# MCU.net
KiCad netlist of a schematic drawn in Altium Designer
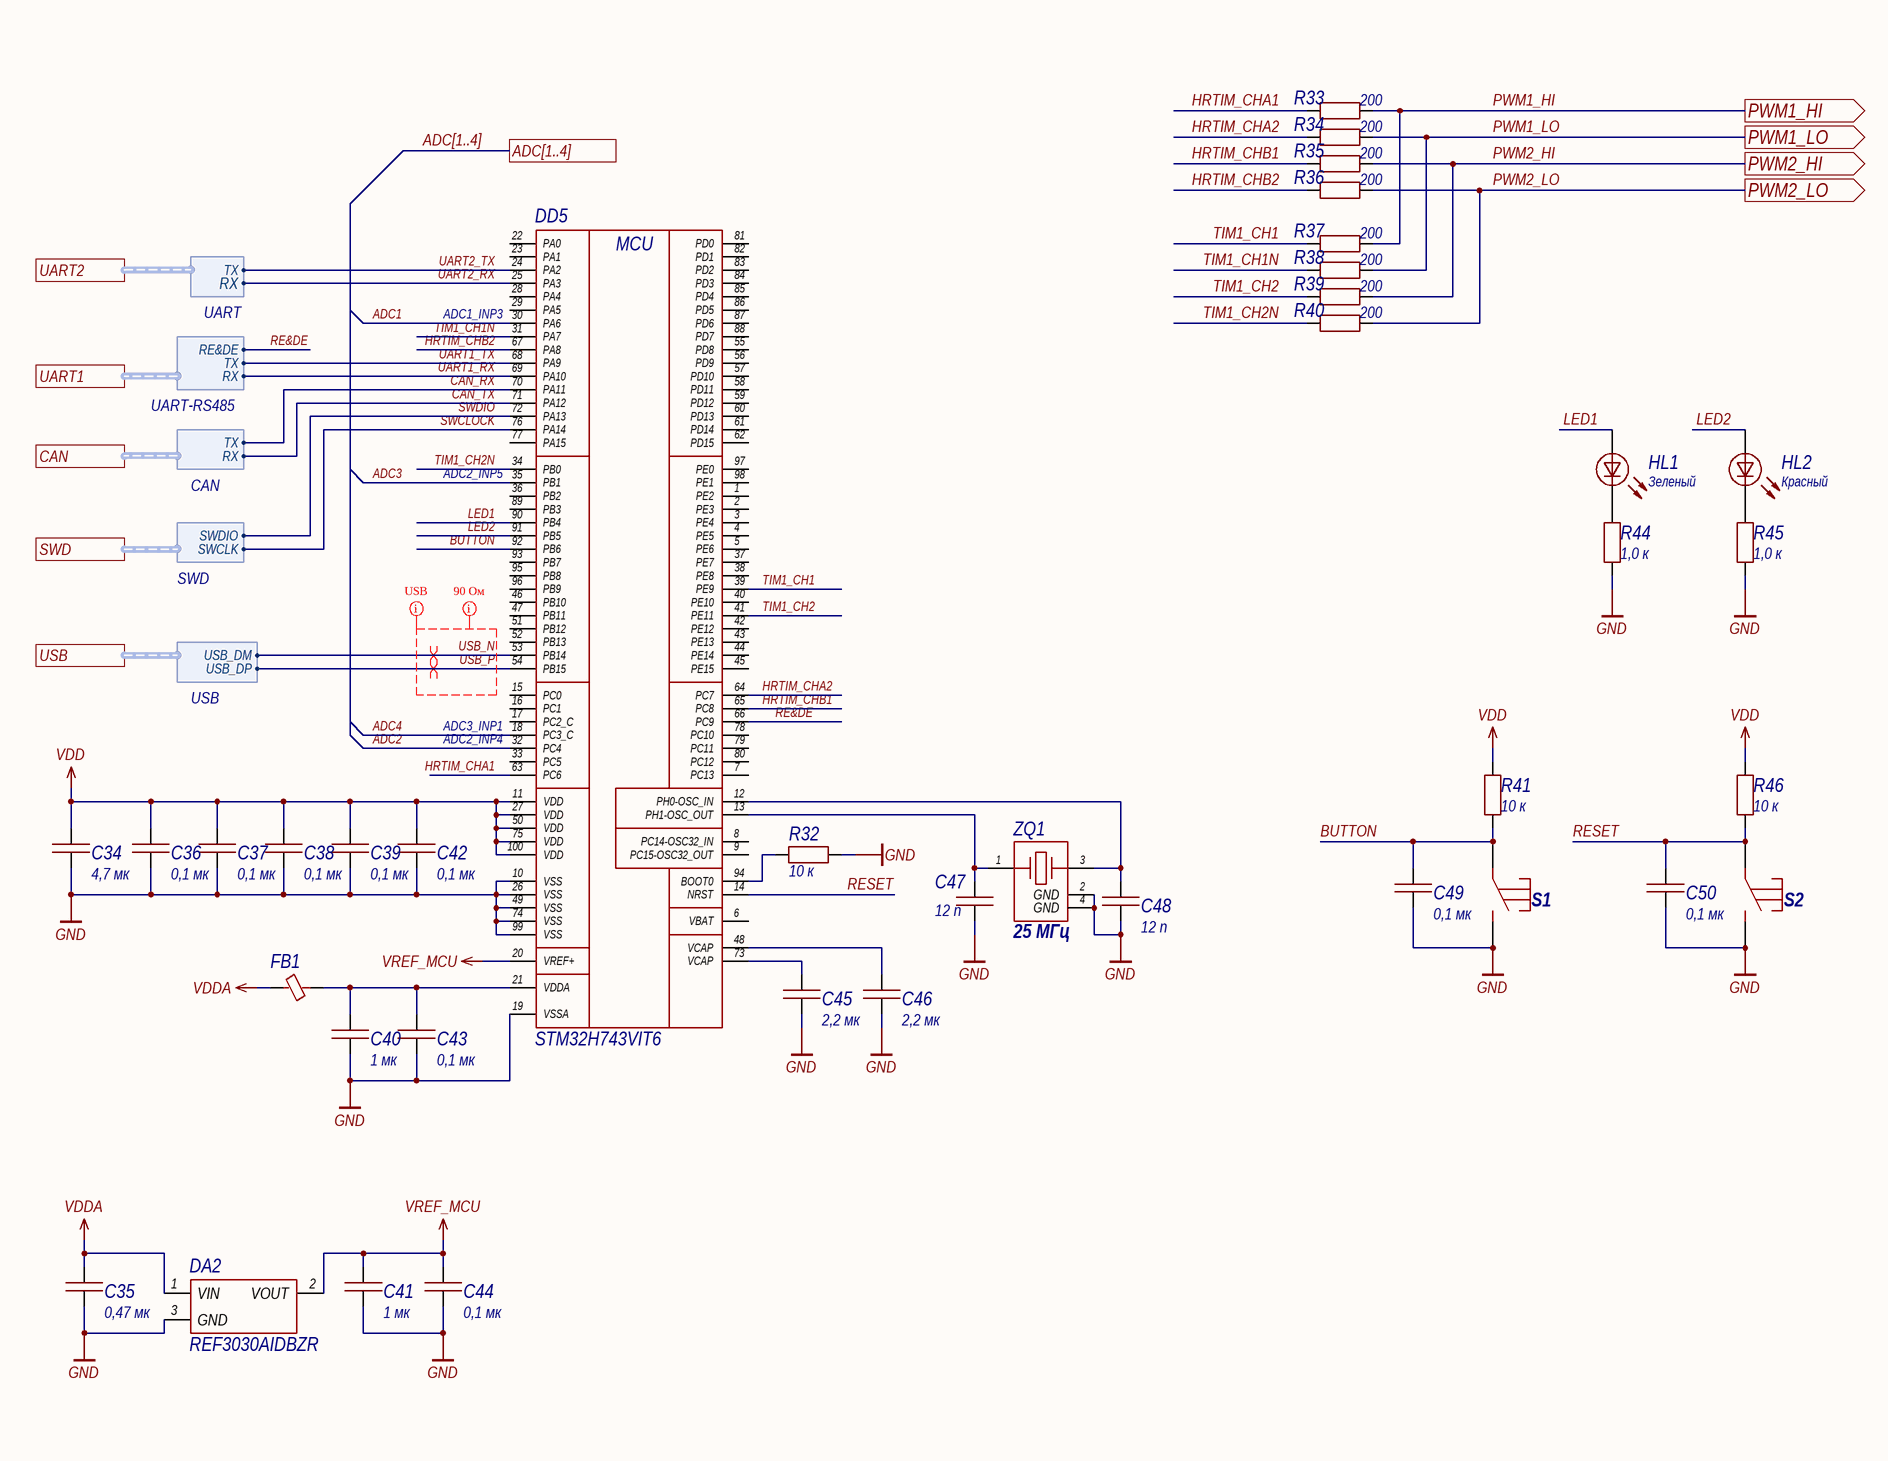
[diagram p0: MCU.SchDoc, left]
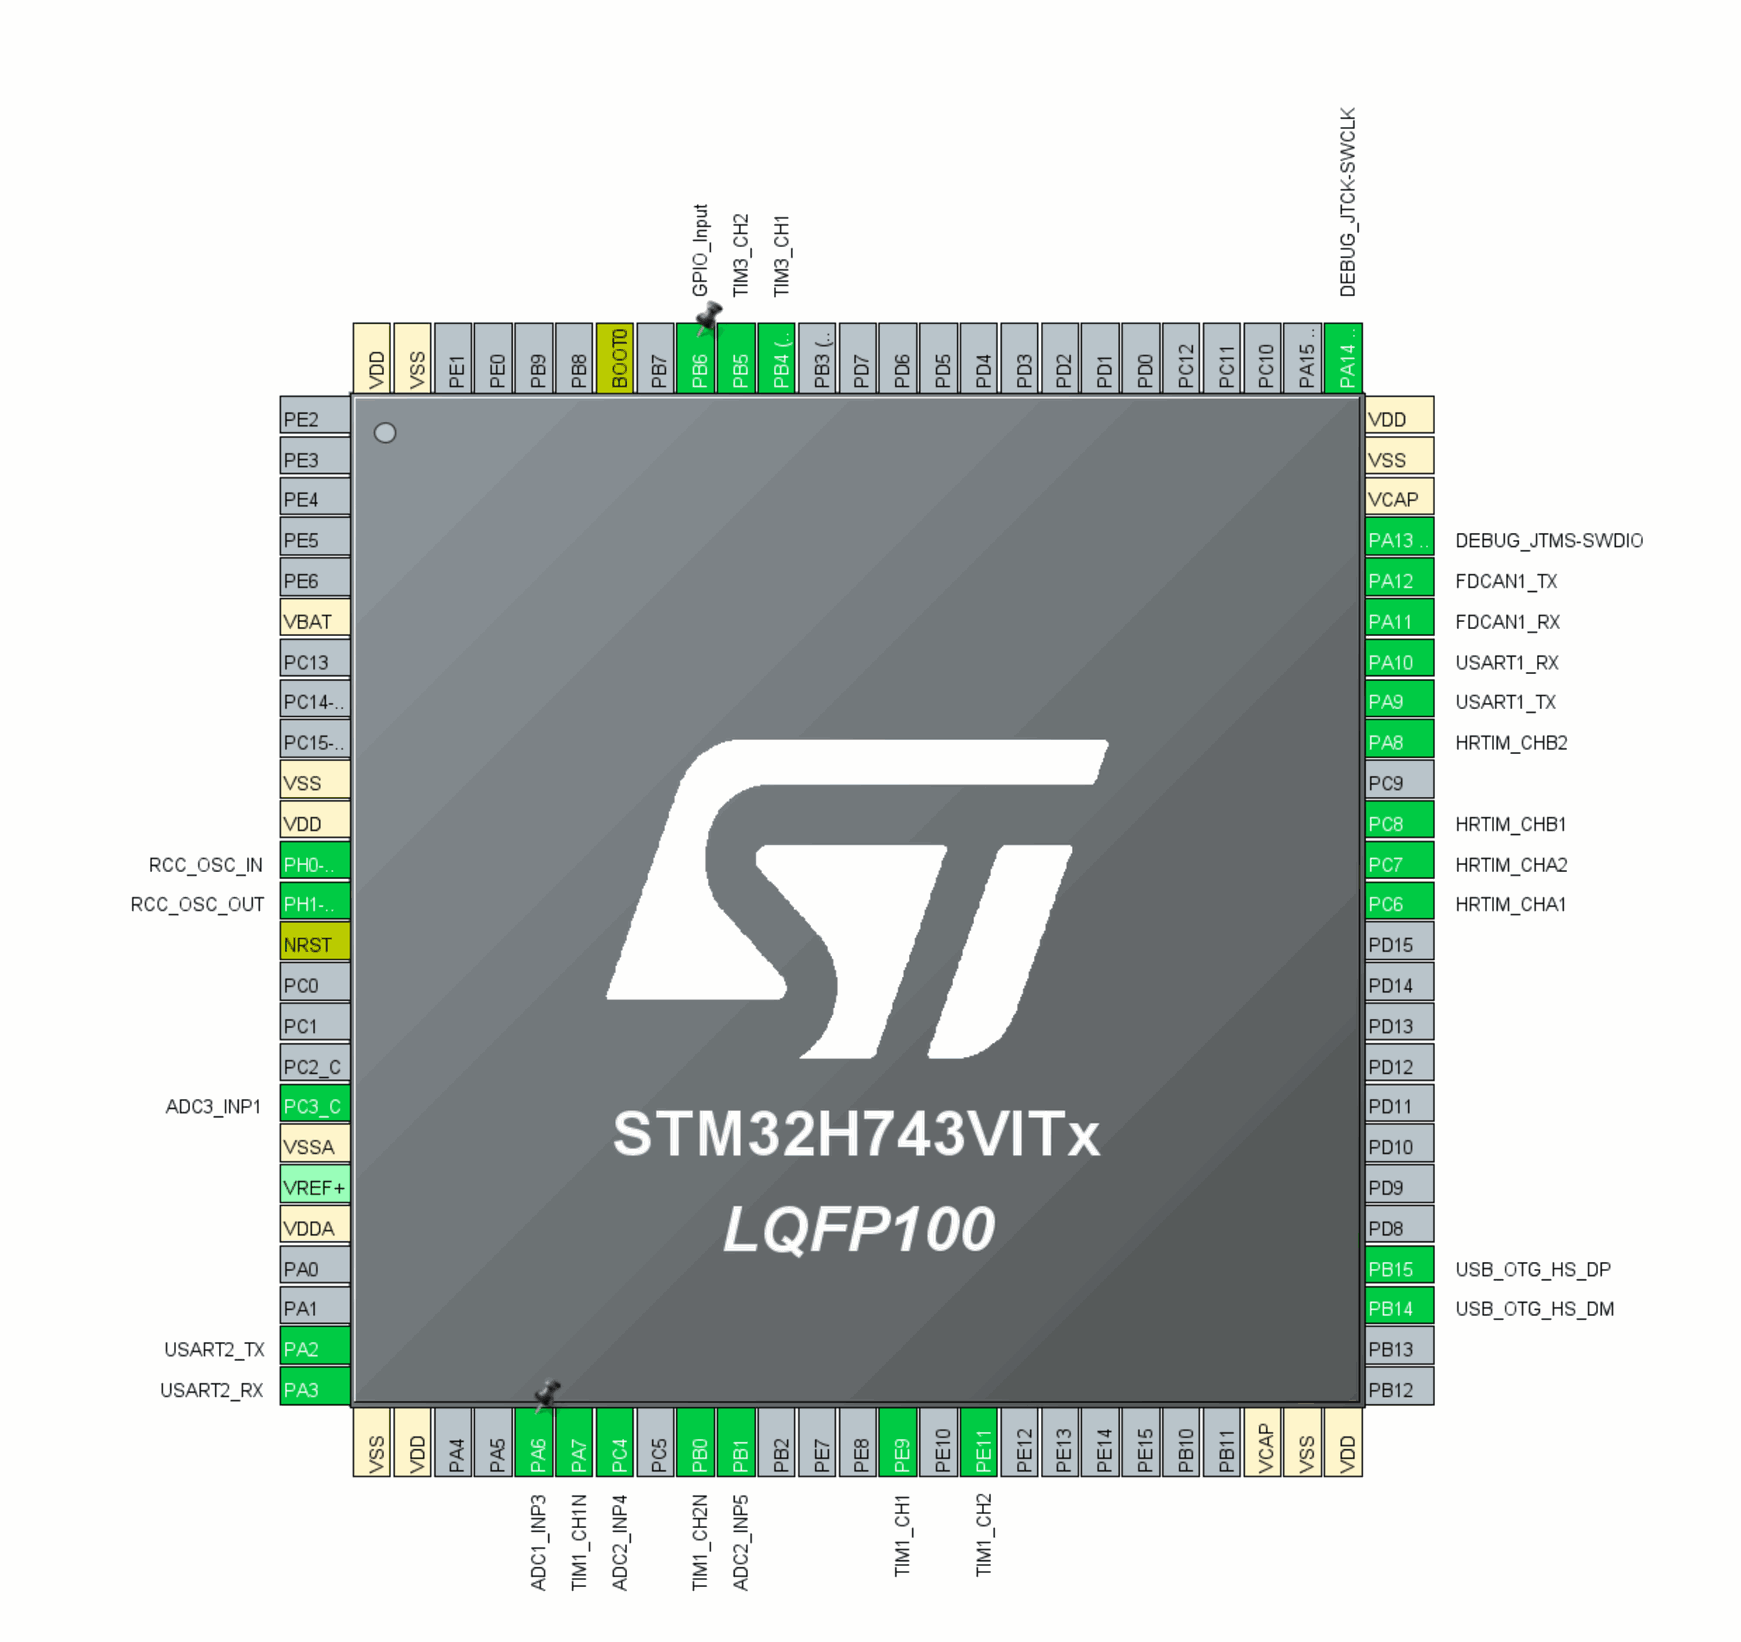
[diagram p1: MCU.SchDoc, right]

(export (version "E")
  (design (tool "Eeschema 10.0.6"))
  (components
    (comp (ref "C34")
      (value "4,7 мк")
      (footprint "1206C")
      (description "Конденсатор 1206C ёмкостью 4,7 мк 10%, 50 В, X7R")
      (fields (field (name "PART NUMBER") "Capacitor_4,7u_10_50V_X7R_1206C") (field (name "TOLERANCE") "10%"))
      (libsource (lib "Hydrolib") (part "Capacitor"))
    )
    (comp (ref "C35")
      (value "0,47 мк")
      (footprint "0603C")
      (description "Конденсатор 0603C ёмкостью 0,47 мк 10%, 50 В, X7R")
      (fields
        (field (name "PART NUMBER") "Capacitor_0,47u_10_50V_X7R_0603C")
        (field (name "TOLERANCE") "10%")
      )
      (libsource (lib "Hydrolib") (part "Capacitor"))
    )
    (comp (ref "C36")
      (value "0,1 мк")
      (footprint "0603C")
      (description "Конденсатор 0603C ёмкостью 0,1 мк 10%, 50 В, X7R")
      (fields (field (name "PART NUMBER") "Capacitor_0,1u_10_50V_X7R_0603C") (field (name "TOLERANCE") "10%"))
      (libsource (lib "Hydrolib") (part "Capacitor"))
    )
    (comp (ref "C37")
      (value "0,1 мк")
      (footprint "0603C")
      (description "Конденсатор 0603C ёмкостью 0,1 мк 10%, 50 В, X7R")
      (fields (field (name "PART NUMBER") "Capacitor_0,1u_10_50V_X7R_0603C") (field (name "TOLERANCE") "10%"))
      (libsource (lib "Hydrolib") (part "Capacitor"))
    )
    (comp (ref "C38")
      (value "0,1 мк")
      (footprint "0603C")
      (description "Конденсатор 0603C ёмкостью 0,1 мк 10%, 50 В, X7R")
      (fields (field (name "PART NUMBER") "Capacitor_0,1u_10_50V_X7R_0603C") (field (name "TOLERANCE") "10%"))
      (libsource (lib "Hydrolib") (part "Capacitor"))
    )
    (comp (ref "C39")
      (value "0,1 мк")
      (footprint "0603C")
      (description "Конденсатор 0603C ёмкостью 0,1 мк 10%, 50 В, X7R")
      (fields (field (name "PART NUMBER") "Capacitor_0,1u_10_50V_X7R_0603C") (field (name "TOLERANCE") "10%"))
      (libsource (lib "Hydrolib") (part "Capacitor"))
    )
    (comp (ref "C40")
      (value "1 мк")
      (footprint "0603C")
      (description "Конденсатор 0603C ёмкостью 1 мк 10%, 25 В, X7R")
      (fields (field (name "PART NUMBER") "Capacitor_1u_10_25V_X7R_0603C") (field (name "TOLERANCE") "10%"))
      (libsource (lib "Hydrolib") (part "Capacitor"))
    )
    (comp (ref "C41")
      (value "1 мк")
      (footprint "0603C")
      (description "Конденсатор 0603C ёмкостью 1 мк 10%, 25 В, X7R")
      (fields (field (name "PART NUMBER") "Capacitor_1u_10_25V_X7R_0603C") (field (name "TOLERANCE") "10%"))
      (libsource (lib "Hydrolib") (part "Capacitor"))
    )
    (comp (ref "C42")
      (value "0,1 мк")
      (footprint "0603C")
      (description "Конденсатор 0603C ёмкостью 0,1 мк 10%, 50 В, X7R")
      (fields (field (name "PART NUMBER") "Capacitor_0,1u_10_50V_X7R_0603C") (field (name "TOLERANCE") "10%"))
      (libsource (lib "Hydrolib") (part "Capacitor"))
    )
    (comp (ref "C43")
      (value "0,1 мк")
      (footprint "0603C")
      (description "Конденсатор 0603C ёмкостью 0,1 мк 10%, 50 В, X7R")
      (fields (field (name "PART NUMBER") "Capacitor_0,1u_10_50V_X7R_0603C") (field (name "TOLERANCE") "10%"))
      (libsource (lib "Hydrolib") (part "Capacitor"))
    )
    (comp (ref "C44")
      (value "0,1 мк")
      (footprint "0603C")
      (description "Конденсатор 0603C ёмкостью 0,1 мк 10%, 50 В, X7R")
      (fields (field (name "PART NUMBER") "Capacitor_0,1u_10_50V_X7R_0603C") (field (name "TOLERANCE") "10%"))
      (libsource (lib "Hydrolib") (part "Capacitor"))
    )
    (comp (ref "C45")
      (value "2,2 мк")
      (footprint "1206C")
      (description "Конденсатор 1206C ёмкостью 2,2 мк 10%, 50 В, X7R")
      (fields (field (name "PART NUMBER") "Capacitor_2,2u_10_50V_X7R_1206C") (field (name "TOLERANCE") "10%"))
      (libsource (lib "Hydrolib") (part "Capacitor"))
    )
    (comp (ref "C46")
      (value "2,2 мк")
      (footprint "1206C")
      (description "Конденсатор 1206C ёмкостью 2,2 мк 10%, 50 В, X7R")
      (fields (field (name "PART NUMBER") "Capacitor_2,2u_10_50V_X7R_1206C") (field (name "TOLERANCE") "10%"))
      (libsource (lib "Hydrolib") (part "Capacitor"))
    )
    (comp (ref "C47")
      (value "12 п")
      (footprint "0603C")
      (description "Конденсатор 0603C ёмкостью 12 п 5%, 50 В, NP0")
      (fields
        (field (name "PART NUMBER") "Capacitor_12p_5_50V_NP0_0603C")
        (field (name "TOLERANCE") "5%")
        (field (name "АВТОР") "glebmih")
      )
      (libsource (lib "Hydrolib") (part "Capacitor"))
    )
    (comp (ref "C48")
      (value "12 п")
      (footprint "0603C")
      (description "Конденсатор 0603C ёмкостью 12 п 5%, 50 В, NP0")
      (fields
        (field (name "PART NUMBER") "Capacitor_12p_5_50V_NP0_0603C")
        (field (name "TOLERANCE") "5%")
        (field (name "АВТОР") "glebmih")
      )
      (libsource (lib "Hydrolib") (part "Capacitor"))
    )
    (comp (ref "C49")
      (value "0,1 мк")
      (footprint "0603C")
      (description "Конденсатор 0603C ёмкостью 0,1 мк 10%, 50 В, X7R")
      (fields (field (name "PART NUMBER") "Capacitor_0,1u_10_50V_X7R_0603C") (field (name "TOLERANCE") "10%"))
      (libsource (lib "Hydrolib") (part "Capacitor"))
    )
    (comp (ref "C50")
      (value "0,1 мк")
      (footprint "0603C")
      (description "Конденсатор 0603C ёмкостью 0,1 мк 10%, 50 В, X7R")
      (fields (field (name "PART NUMBER") "Capacitor_0,1u_10_50V_X7R_0603C") (field (name "TOLERANCE") "10%"))
      (libsource (lib "Hydrolib") (part "Capacitor"))
    )
    (comp (ref "DA2")
      (value "REF3030AIDBZR")
      (footprint "SOT23-3")
      (description "Источник опорного напряжения, 3В")
      (fields (field (name "АВТОР") "glebmih"))
      (libsource (lib "Hydrolib") (part "REF3030AIDBZR"))
    )
    (comp (ref "DD5")
      (value "STM32H743VIT6")
      (footprint "LQFP100")
      (description "Микроконтроллер, 32-Бит, Cortex-M7, 480МГц, 2Мб Flash, 1Мб SRAM, 82 I/O")
      (fields (field (name "MF") "STMicroelectronics") (field (name "АВТОР") "glebmih"))
      (libsource (lib "Hydrolib") (part "STM32H743VIT6"))
    )
    (comp (ref "FB1")
      (value "BLM18AG102SN1D")
      (footprint "0603L")
      (description "Дроссель подавления ЭМП")
      (fields (field (name "АВТОР") "glebmih"))
      (libsource (lib "Hydrolib") (part "Ferrite_bead"))
    )
    (comp (ref "HL1")
      (value "Зеленый")
      (footprint "0805D")
      (description "Светодиод")
      (fields (field (name "PART NUMBER") "LED"))
      (libsource (lib "Hydrolib") (part "LED"))
    )
    (comp (ref "HL2")
      (value "Красный")
      (footprint "0805D")
      (description "Светодиод")
      (fields (field (name "PART NUMBER") "LED"))
      (libsource (lib "Hydrolib") (part "LED"))
    )
    (comp (ref "R32")
      (value "10 к")
      (footprint "0603R")
      (description "Резистор номиналом 10 кОм 1%")
      (fields (field (name "PART NUMBER") "Resistor_10k_1_0603") (field (name "TOLERANCE") "1%"))
      (libsource (lib "") (part "Resistor_1"))
    )
    (comp (ref "R33")
      (value "200")
      (footprint "0603R")
      (description "Резистор номиналом 200 Ом 1%")
      (fields (field (name "PART NUMBER") "Resistor_200_1_0603") (field (name "TOLERANCE") "1%"))
      (libsource (lib "Hydrolib") (part "Resistor"))
    )
    (comp (ref "R34")
      (value "200")
      (footprint "0603R")
      (description "Резистор номиналом 200 Ом 1%")
      (fields (field (name "PART NUMBER") "Resistor_200_1_0603") (field (name "TOLERANCE") "1%"))
      (libsource (lib "Hydrolib") (part "Resistor"))
    )
    (comp (ref "R35")
      (value "200")
      (footprint "0603R")
      (description "Резистор номиналом 200 Ом 1%")
      (fields (field (name "PART NUMBER") "Resistor_200_1_0603") (field (name "TOLERANCE") "1%"))
      (libsource (lib "Hydrolib") (part "Resistor"))
    )
    (comp (ref "R36")
      (value "200")
      (footprint "0603R")
      (description "Резистор номиналом 200 Ом 1%")
      (fields (field (name "PART NUMBER") "Resistor_200_1_0603") (field (name "TOLERANCE") "1%"))
      (libsource (lib "Hydrolib") (part "Resistor"))
    )
    (comp (ref "R37")
      (value "200")
      (footprint "0603R")
      (description "Резистор номиналом 200 Ом 1%")
      (fields (field (name "PART NUMBER") "Resistor_200_1_0603") (field (name "TOLERANCE") "1%"))
      (libsource (lib "Hydrolib") (part "Resistor"))
    )
    (comp (ref "R38")
      (value "200")
      (footprint "0603R")
      (description "Резистор номиналом 200 Ом 1%")
      (fields (field (name "PART NUMBER") "Resistor_200_1_0603") (field (name "TOLERANCE") "1%"))
      (libsource (lib "Hydrolib") (part "Resistor"))
    )
    (comp (ref "R39")
      (value "200")
      (footprint "0603R")
      (description "Резистор номиналом 200 Ом 1%")
      (fields (field (name "PART NUMBER") "Resistor_200_1_0603") (field (name "TOLERANCE") "1%"))
      (libsource (lib "Hydrolib") (part "Resistor"))
    )
    (comp (ref "R40")
      (value "200")
      (footprint "0603R")
      (description "Резистор номиналом 200 Ом 1%")
      (fields (field (name "PART NUMBER") "Resistor_200_1_0603") (field (name "TOLERANCE") "1%"))
      (libsource (lib "Hydrolib") (part "Resistor"))
    )
    (comp (ref "R41")
      (value "10 к")
      (footprint "0603R")
      (description "Резистор номиналом 10 кОм 1%")
      (fields (field (name "PART NUMBER") "Resistor_10k_1_0603") (field (name "TOLERANCE") "1%"))
      (libsource (lib "") (part "Resistor_2"))
    )
    (comp (ref "R44")
      (value "1,0 к")
      (footprint "0603R")
      (description "Резистор номиналом 1,0 кОм 1%")
      (fields (field (name "PART NUMBER") "Resistor_1.0k_1_0603") (field (name "TOLERANCE") "1%"))
      (libsource (lib "") (part "Resistor_2"))
    )
    (comp (ref "R45")
      (value "1,0 к")
      (footprint "0603R")
      (description "Резистор номиналом 1,0 кОм 1%")
      (fields (field (name "PART NUMBER") "Resistor_1.0k_1_0603") (field (name "TOLERANCE") "1%"))
      (libsource (lib "") (part "Resistor_2"))
    )
    (comp (ref "R46")
      (value "10 к")
      (footprint "0603R")
      (description "Резистор номиналом 10 кОм 1%")
      (fields (field (name "PART NUMBER") "Resistor_10k_1_0603") (field (name "TOLERANCE") "1%"))
      (libsource (lib "") (part "Resistor_2"))
    )
    (comp (ref "S1")
      (value "TSS-TD-19XA-XTR")
      (footprint "TSS-TD-19XA-XTR")
      (description "Тактовая кнопка")
      (fields (field (name "АВТОР") "glebmih"))
      (libsource (lib "Hydrolib") (part "Tact_button"))
    )
    (comp (ref "S2")
      (value "TSS-TD-19XA-XTR")
      (footprint "TSS-TD-19XA-XTR")
      (description "Тактовая кнопка")
      (fields (field (name "АВТОР") "glebmih"))
      (libsource (lib "Hydrolib") (part "Tact_button"))
    )
    (comp (ref "ZQ1")
      (value "25 МГц")
      (footprint "X322525MOB4SI")
      (description "Кварцевый резонатор SMD 25 МГц ±10ppm SMD-3225_4P")
      (fields (field (name "PART NUMBER") "X322525MOB4SI") (field (name "АВТОР") "rreali"))
      (libsource (lib "Hydrolib") (part "XTAL_1-3_GND"))
    )
  )
  (nets
    (net (code "6") (name "/ADC1") (class "Default")
      (node (ref "DD5") (pin "30") (pinfunction "PA6_30") (pintype "passive"))
    )
    (net (code "7") (name "/ADC2") (class "Default")
      (node (ref "DD5") (pin "32") (pinfunction "PC4_32") (pintype "passive"))
    )
    (net (code "8") (name "/ADC3") (class "Default")
      (node (ref "DD5") (pin "35") (pinfunction "PB1_35") (pintype "passive"))
    )
    (net (code "9") (name "/ADC4") (class "Default")
      (node (ref "DD5") (pin "18") (pinfunction "PC3_C_18") (pintype "passive"))
    )
    (net (code "11") (name "/BUTTON") (class "Default")
      (node (ref "C49") (pin "2") (pinfunction "2_2") (pintype "passive"))
      (node (ref "DD5") (pin "92") (pinfunction "PB6_92") (pintype "passive"))
      (node (ref "R41") (pin "1") (pinfunction "1_1") (pintype "passive"))
      (node (ref "S1") (pin "1") (pinfunction "1_1") (pintype "passive"))
    )
    (net (code "12") (name "/CAN_RX") (class "Default")
      (node (ref "DD5") (pin "70") (pinfunction "PA11_70") (pintype "passive"))
    )
    (net (code "13") (name "/CAN_TX") (class "Default")
      (node (ref "DD5") (pin "71") (pinfunction "PA12_71") (pintype "passive"))
    )
    (net (code "14") (name "/HRTIM_CHA1") (class "Default")
      (node (ref "DD5") (pin "63") (pinfunction "PC6_63") (pintype "passive"))
      (node (ref "R33") (pin "1") (pinfunction "1_1") (pintype "passive"))
    )
    (net (code "15") (name "/HRTIM_CHA2") (class "Default")
      (node (ref "DD5") (pin "64") (pinfunction "PC7_64") (pintype "passive"))
      (node (ref "R34") (pin "1") (pinfunction "1_1") (pintype "passive"))
    )
    (net (code "16") (name "/HRTIM_CHB1") (class "Default")
      (node (ref "DD5") (pin "65") (pinfunction "PC8_65") (pintype "passive"))
      (node (ref "R35") (pin "1") (pinfunction "1_1") (pintype "passive"))
    )
    (net (code "17") (name "/HRTIM_CHB2") (class "Default")
      (node (ref "DD5") (pin "67") (pinfunction "PA8_67") (pintype "passive"))
      (node (ref "R36") (pin "1") (pinfunction "1_1") (pintype "passive"))
    )
    (net (code "18") (name "/LED1") (class "Default")
      (node (ref "DD5") (pin "90") (pinfunction "PB4_90") (pintype "passive"))
      (node (ref "HL1") (pin "1") (pinfunction "1_1") (pintype "passive"))
    )
    (net (code "19") (name "/LED2") (class "Default")
      (node (ref "DD5") (pin "91") (pinfunction "PB5_91") (pintype "passive"))
      (node (ref "HL2") (pin "1") (pinfunction "1_1") (pintype "passive"))
    )
    (net (code "20") (name "/PWM1_HI") (class "Default")
      (node (ref "R33") (pin "2") (pinfunction "2_2") (pintype "passive"))
      (node (ref "R37") (pin "2") (pinfunction "2_2") (pintype "passive"))
    )
    (net (code "21") (name "/PWM1_LO") (class "Default")
      (node (ref "R34") (pin "2") (pinfunction "2_2") (pintype "passive"))
      (node (ref "R38") (pin "2") (pinfunction "2_2") (pintype "passive"))
    )
    (net (code "22") (name "/PWM2_HI") (class "Default")
      (node (ref "R35") (pin "2") (pinfunction "2_2") (pintype "passive"))
      (node (ref "R39") (pin "2") (pinfunction "2_2") (pintype "passive"))
    )
    (net (code "23") (name "/PWM2_LO") (class "Default")
      (node (ref "R36") (pin "2") (pinfunction "2_2") (pintype "passive"))
      (node (ref "R40") (pin "2") (pinfunction "2_2") (pintype "passive"))
    )
    (net (code "24") (name "/RE&DE") (class "Default")
      (node (ref "DD5") (pin "66") (pinfunction "PC9_66") (pintype "passive"))
    )
    (net (code "25") (name "/RESET") (class "Default")
      (node (ref "C50") (pin "2") (pinfunction "2_2") (pintype "passive"))
      (node (ref "DD5") (pin "14") (pinfunction "NRST_14") (pintype "passive"))
      (node (ref "R46") (pin "1") (pinfunction "1_1") (pintype "passive"))
      (node (ref "S2") (pin "1") (pinfunction "1_1") (pintype "passive"))
    )
    (net (code "26") (name "/SWCLOCK") (class "Default")
      (node (ref "DD5") (pin "76") (pinfunction "PA14_76") (pintype "passive"))
    )
    (net (code "27") (name "/SWDIO") (class "Default")
      (node (ref "DD5") (pin "72") (pinfunction "PA13_72") (pintype "passive"))
    )
    (net (code "28") (name "/TIM1_CH1") (class "Default")
      (node (ref "DD5") (pin "39") (pinfunction "PE9_39") (pintype "passive"))
      (node (ref "R37") (pin "1") (pinfunction "1_1") (pintype "passive"))
    )
    (net (code "29") (name "/TIM1_CH1N") (class "Default")
      (node (ref "DD5") (pin "31") (pinfunction "PA7_31") (pintype "passive"))
      (node (ref "R38") (pin "1") (pinfunction "1_1") (pintype "passive"))
    )
    (net (code "30") (name "/TIM1_CH2") (class "Default")
      (node (ref "DD5") (pin "41") (pinfunction "PE11_41") (pintype "passive"))
      (node (ref "R39") (pin "1") (pinfunction "1_1") (pintype "passive"))
    )
    (net (code "31") (name "/TIM1_CH2N") (class "Default")
      (node (ref "DD5") (pin "34") (pinfunction "PB0_34") (pintype "passive"))
      (node (ref "R40") (pin "1") (pinfunction "1_1") (pintype "passive"))
    )
    (net (code "32") (name "/UART1_RX") (class "Default")
      (node (ref "DD5") (pin "69") (pinfunction "PA10_69") (pintype "passive"))
    )
    (net (code "33") (name "/UART1_TX") (class "Default")
      (node (ref "DD5") (pin "68") (pinfunction "PA9_68") (pintype "passive"))
    )
    (net (code "34") (name "/UART2_RX") (class "Default")
      (node (ref "DD5") (pin "25") (pinfunction "PA3_25") (pintype "passive"))
    )
    (net (code "35") (name "/UART2_TX") (class "Default")
      (node (ref "DD5") (pin "24") (pinfunction "PA2_24") (pintype "passive"))
    )
    (net (code "36") (name "/USB_N") (class "Default")
      (node (ref "DD5") (pin "53") (pinfunction "PB14_53") (pintype "passive"))
    )
    (net (code "37") (name "/USB_P") (class "Default")
      (node (ref "DD5") (pin "54") (pinfunction "PB15_54") (pintype "passive"))
    )
    (net (code "43") (name "GND") (class "Default")
      (node (ref "C34") (pin "1") (pinfunction "1_1") (pintype "passive"))
      (node (ref "C35") (pin "1") (pinfunction "1_1") (pintype "passive"))
      (node (ref "C36") (pin "1") (pinfunction "1_1") (pintype "passive"))
      (node (ref "C37") (pin "1") (pinfunction "1_1") (pintype "passive"))
      (node (ref "C38") (pin "1") (pinfunction "1_1") (pintype "passive"))
      (node (ref "C39") (pin "1") (pinfunction "1_1") (pintype "passive"))
      (node (ref "C40") (pin "1") (pinfunction "1_1") (pintype "passive"))
      (node (ref "C41") (pin "1") (pinfunction "1_1") (pintype "passive"))
      (node (ref "C42") (pin "1") (pinfunction "1_1") (pintype "passive"))
      (node (ref "C43") (pin "1") (pinfunction "1_1") (pintype "passive"))
      (node (ref "C44") (pin "1") (pinfunction "1_1") (pintype "passive"))
      (node (ref "C45") (pin "1") (pinfunction "1_1") (pintype "passive"))
      (node (ref "C46") (pin "1") (pinfunction "1_1") (pintype "passive"))
      (node (ref "C47") (pin "1") (pinfunction "1_1") (pintype "passive"))
      (node (ref "C48") (pin "1") (pinfunction "1_1") (pintype "passive"))
      (node (ref "C49") (pin "1") (pinfunction "1_1") (pintype "passive"))
      (node (ref "C50") (pin "1") (pinfunction "1_1") (pintype "passive"))
      (node (ref "DA2") (pin "3") (pinfunction "GND_3") (pintype "passive"))
      (node (ref "DD5") (pin "10") (pinfunction "VSS_10") (pintype "power_in"))
      (node (ref "DD5") (pin "19") (pinfunction "VSSA_19") (pintype "power_in"))
      (node (ref "DD5") (pin "26") (pinfunction "VSS_26") (pintype "power_in"))
      (node (ref "DD5") (pin "49") (pinfunction "VSS_49") (pintype "power_in"))
      (node (ref "DD5") (pin "74") (pinfunction "VSS_74") (pintype "power_in"))
      (node (ref "DD5") (pin "99") (pinfunction "VSS_99") (pintype "power_in"))
      (node (ref "R32") (pin "1") (pinfunction "1_1") (pintype "passive"))
      (node (ref "R44") (pin "1") (pinfunction "1_1") (pintype "passive"))
      (node (ref "R45") (pin "1") (pinfunction "1_1") (pintype "passive"))
      (node (ref "S1") (pin "2") (pinfunction "2_2") (pintype "passive"))
      (node (ref "S2") (pin "2") (pinfunction "2_2") (pintype "passive"))
      (node (ref "ZQ1") (pin "2") (pinfunction "GND_2") (pintype "passive"))
      (node (ref "ZQ1") (pin "4") (pinfunction "GND_4") (pintype "passive"))
    )
    (net (code "44") (name "Net-(C45-Pad2)") (class "Default")
      (node (ref "C45") (pin "2") (pinfunction "2_2") (pintype "passive"))
      (node (ref "DD5") (pin "73") (pinfunction "VCAP_73") (pintype "power_in"))
    )
    (net (code "45") (name "Net-(C46-Pad2)") (class "Default")
      (node (ref "C46") (pin "2") (pinfunction "2_2") (pintype "passive"))
      (node (ref "DD5") (pin "48") (pinfunction "VCAP_48") (pintype "power_in"))
    )
    (net (code "46") (name "Net-(DD5-BOOT0)") (class "Default")
      (node (ref "DD5") (pin "94") (pinfunction "BOOT0_94") (pintype "passive"))
      (node (ref "R32") (pin "2") (pinfunction "2_2") (pintype "passive"))
    )
    (net (code "47") (name "Net-(DD5-PH0-OSC_IN)") (class "Default")
      (node (ref "C48") (pin "2") (pinfunction "2_2") (pintype "passive"))
      (node (ref "DD5") (pin "12") (pinfunction "PH0-OSC_IN_12") (pintype "passive"))
      (node (ref "ZQ1") (pin "3") (pinfunction "3_3") (pintype "passive"))
    )
    (net (code "48") (name "Net-(DD5-PH1-OSC_OUT)") (class "Default")
      (node (ref "C47") (pin "2") (pinfunction "2_2") (pintype "passive"))
      (node (ref "DD5") (pin "13") (pinfunction "PH1-OSC_OUT_13") (pintype "passive"))
      (node (ref "ZQ1") (pin "1") (pinfunction "1_1") (pintype "passive"))
    )
    (net (code "49") (name "Net-(DD5-VDDA)") (class "Default")
      (node (ref "C40") (pin "2") (pinfunction "2_2") (pintype "passive"))
      (node (ref "C43") (pin "2") (pinfunction "2_2") (pintype "passive"))
      (node (ref "DD5") (pin "21") (pinfunction "VDDA_21") (pintype "power_in"))
      (node (ref "FB1") (pin "2") (pinfunction "2_2") (pintype "passive"))
    )
    (net (code "50") (name "Net-(HL1-Pad2)") (class "Default")
      (node (ref "HL1") (pin "2") (pinfunction "2_2") (pintype "passive"))
      (node (ref "R44") (pin "2") (pinfunction "2_2") (pintype "passive"))
    )
    (net (code "51") (name "Net-(HL2-Pad2)") (class "Default")
      (node (ref "HL2") (pin "2") (pinfunction "2_2") (pintype "passive"))
      (node (ref "R45") (pin "2") (pinfunction "2_2") (pintype "passive"))
    )
    (net (code "52") (name "VDD") (class "Default")
      (node (ref "C34") (pin "2") (pinfunction "2_2") (pintype "passive"))
      (node (ref "C36") (pin "2") (pinfunction "2_2") (pintype "passive"))
      (node (ref "C37") (pin "2") (pinfunction "2_2") (pintype "passive"))
      (node (ref "C38") (pin "2") (pinfunction "2_2") (pintype "passive"))
      (node (ref "C39") (pin "2") (pinfunction "2_2") (pintype "passive"))
      (node (ref "C42") (pin "2") (pinfunction "2_2") (pintype "passive"))
      (node (ref "DD5") (pin "100") (pinfunction "VDD_100") (pintype "power_in"))
      (node (ref "DD5") (pin "11") (pinfunction "VDD_11") (pintype "power_in"))
      (node (ref "DD5") (pin "27") (pinfunction "VDD_27") (pintype "power_in"))
      (node (ref "DD5") (pin "50") (pinfunction "VDD_50") (pintype "power_in"))
      (node (ref "DD5") (pin "75") (pinfunction "VDD_75") (pintype "power_in"))
      (node (ref "R41") (pin "2") (pinfunction "2_2") (pintype "passive"))
      (node (ref "R46") (pin "2") (pinfunction "2_2") (pintype "passive"))
    )
    (net (code "53") (name "VDDA") (class "Default")
      (node (ref "C35") (pin "2") (pinfunction "2_2") (pintype "passive"))
      (node (ref "DA2") (pin "1") (pinfunction "VIN_1") (pintype "passive"))
      (node (ref "FB1") (pin "1") (pinfunction "1_1") (pintype "passive"))
    )
    (net (code "54") (name "VREF_MCU") (class "Default")
      (node (ref "C41") (pin "2") (pinfunction "2_2") (pintype "passive"))
      (node (ref "C44") (pin "2") (pinfunction "2_2") (pintype "passive"))
      (node (ref "DA2") (pin "2") (pinfunction "VOUT_2") (pintype "passive"))
      (node (ref "DD5") (pin "20") (pinfunction "VREF+_20") (pintype "power_in"))
    )
    (net (code "55") (name "unconnected-(DD5-PA0-Pad22)") (class "Default")
      (node (ref "DD5") (pin "22") (pinfunction "PA0_22") (pintype "passive"))
    )
    (net (code "56") (name "unconnected-(DD5-PA1-Pad23)") (class "Default")
      (node (ref "DD5") (pin "23") (pinfunction "PA1_23") (pintype "passive"))
    )
    (net (code "57") (name "unconnected-(DD5-PA4-Pad28)") (class "Default")
      (node (ref "DD5") (pin "28") (pinfunction "PA4_28") (pintype "passive"))
    )
    (net (code "58") (name "unconnected-(DD5-PA5-Pad29)") (class "Default")
      (node (ref "DD5") (pin "29") (pinfunction "PA5_29") (pintype "passive"))
    )
    (net (code "59") (name "unconnected-(DD5-PA15-Pad77)") (class "Default")
      (node (ref "DD5") (pin "77") (pinfunction "PA15_77") (pintype "passive"))
    )
    (net (code "60") (name "unconnected-(DD5-PB2-Pad36)") (class "Default")
      (node (ref "DD5") (pin "36") (pinfunction "PB2_36") (pintype "passive"))
    )
    (net (code "61") (name "unconnected-(DD5-PB3-Pad89)") (class "Default")
      (node (ref "DD5") (pin "89") (pinfunction "PB3_89") (pintype "passive"))
    )
    (net (code "62") (name "unconnected-(DD5-PB7-Pad93)") (class "Default")
      (node (ref "DD5") (pin "93") (pinfunction "PB7_93") (pintype "passive"))
    )
    (net (code "63") (name "unconnected-(DD5-PB8-Pad95)") (class "Default")
      (node (ref "DD5") (pin "95") (pinfunction "PB8_95") (pintype "passive"))
    )
    (net (code "64") (name "unconnected-(DD5-PB9-Pad96)") (class "Default")
      (node (ref "DD5") (pin "96") (pinfunction "PB9_96") (pintype "passive"))
    )
    (net (code "65") (name "unconnected-(DD5-PB10-Pad46)") (class "Default")
      (node (ref "DD5") (pin "46") (pinfunction "PB10_46") (pintype "passive"))
    )
    (net (code "66") (name "unconnected-(DD5-PB11-Pad47)") (class "Default")
      (node (ref "DD5") (pin "47") (pinfunction "PB11_47") (pintype "passive"))
    )
    (net (code "67") (name "unconnected-(DD5-PB12-Pad51)") (class "Default")
      (node (ref "DD5") (pin "51") (pinfunction "PB12_51") (pintype "passive"))
    )
    (net (code "68") (name "unconnected-(DD5-PB13-Pad52)") (class "Default")
      (node (ref "DD5") (pin "52") (pinfunction "PB13_52") (pintype "passive"))
    )
    (net (code "69") (name "unconnected-(DD5-PC0-Pad15)") (class "Default")
      (node (ref "DD5") (pin "15") (pinfunction "PC0_15") (pintype "passive"))
    )
    (net (code "70") (name "unconnected-(DD5-PC1-Pad16)") (class "Default")
      (node (ref "DD5") (pin "16") (pinfunction "PC1_16") (pintype "passive"))
    )
    (net (code "71") (name "unconnected-(DD5-PC2_C-Pad17)") (class "Default")
      (node (ref "DD5") (pin "17") (pinfunction "PC2_C_17") (pintype "passive"))
    )
    (net (code "72") (name "unconnected-(DD5-PC5-Pad33)") (class "Default")
      (node (ref "DD5") (pin "33") (pinfunction "PC5_33") (pintype "passive"))
    )
    (net (code "73") (name "unconnected-(DD5-PC10-Pad78)") (class "Default")
      (node (ref "DD5") (pin "78") (pinfunction "PC10_78") (pintype "passive"))
    )
    (net (code "74") (name "unconnected-(DD5-PC11-Pad79)") (class "Default")
      (node (ref "DD5") (pin "79") (pinfunction "PC11_79") (pintype "passive"))
    )
    (net (code "75") (name "unconnected-(DD5-PC12-Pad80)") (class "Default")
      (node (ref "DD5") (pin "80") (pinfunction "PC12_80") (pintype "passive"))
    )
    (net (code "76") (name "unconnected-(DD5-PC13-Pad7)") (class "Default")
      (node (ref "DD5") (pin "7") (pinfunction "PC13_7") (pintype "passive"))
    )
    (net (code "77") (name "unconnected-(DD5-PC14-OSC32_IN-Pad8)") (class "Default")
      (node (ref "DD5") (pin "8") (pinfunction "PC14-OSC32_IN_8") (pintype "passive"))
    )
    (net (code "78") (name "unconnected-(DD5-PC15-OSC32_OUT-Pad9)") (class "Default")
      (node (ref "DD5") (pin "9") (pinfunction "PC15-OSC32_OUT_9") (pintype "passive"))
    )
    (net (code "79") (name "unconnected-(DD5-PD0-Pad81)") (class "Default")
      (node (ref "DD5") (pin "81") (pinfunction "PD0_81") (pintype "passive"))
    )
    (net (code "80") (name "unconnected-(DD5-PD1-Pad82)") (class "Default")
      (node (ref "DD5") (pin "82") (pinfunction "PD1_82") (pintype "passive"))
    )
    (net (code "81") (name "unconnected-(DD5-PD2-Pad83)") (class "Default")
      (node (ref "DD5") (pin "83") (pinfunction "PD2_83") (pintype "passive"))
    )
    (net (code "82") (name "unconnected-(DD5-PD3-Pad84)") (class "Default")
      (node (ref "DD5") (pin "84") (pinfunction "PD3_84") (pintype "passive"))
    )
    (net (code "83") (name "unconnected-(DD5-PD4-Pad85)") (class "Default")
      (node (ref "DD5") (pin "85") (pinfunction "PD4_85") (pintype "passive"))
    )
    (net (code "84") (name "unconnected-(DD5-PD5-Pad86)") (class "Default")
      (node (ref "DD5") (pin "86") (pinfunction "PD5_86") (pintype "passive"))
    )
    (net (code "85") (name "unconnected-(DD5-PD6-Pad87)") (class "Default")
      (node (ref "DD5") (pin "87") (pinfunction "PD6_87") (pintype "passive"))
    )
    (net (code "86") (name "unconnected-(DD5-PD7-Pad88)") (class "Default")
      (node (ref "DD5") (pin "88") (pinfunction "PD7_88") (pintype "passive"))
    )
    (net (code "87") (name "unconnected-(DD5-PD8-Pad55)") (class "Default")
      (node (ref "DD5") (pin "55") (pinfunction "PD8_55") (pintype "passive"))
    )
    (net (code "88") (name "unconnected-(DD5-PD9-Pad56)") (class "Default")
      (node (ref "DD5") (pin "56") (pinfunction "PD9_56") (pintype "passive"))
    )
    (net (code "89") (name "unconnected-(DD5-PD10-Pad57)") (class "Default")
      (node (ref "DD5") (pin "57") (pinfunction "PD10_57") (pintype "passive"))
    )
    (net (code "90") (name "unconnected-(DD5-PD11-Pad58)") (class "Default")
      (node (ref "DD5") (pin "58") (pinfunction "PD11_58") (pintype "passive"))
    )
    (net (code "91") (name "unconnected-(DD5-PD12-Pad59)") (class "Default")
      (node (ref "DD5") (pin "59") (pinfunction "PD12_59") (pintype "passive"))
    )
    (net (code "92") (name "unconnected-(DD5-PD13-Pad60)") (class "Default")
      (node (ref "DD5") (pin "60") (pinfunction "PD13_60") (pintype "passive"))
    )
    (net (code "93") (name "unconnected-(DD5-PD14-Pad61)") (class "Default")
      (node (ref "DD5") (pin "61") (pinfunction "PD14_61") (pintype "passive"))
    )
    (net (code "94") (name "unconnected-(DD5-PD15-Pad62)") (class "Default")
      (node (ref "DD5") (pin "62") (pinfunction "PD15_62") (pintype "passive"))
    )
    (net (code "95") (name "unconnected-(DD5-PE0-Pad97)") (class "Default")
      (node (ref "DD5") (pin "97") (pinfunction "PE0_97") (pintype "passive"))
    )
    (net (code "96") (name "unconnected-(DD5-PE1-Pad98)") (class "Default")
      (node (ref "DD5") (pin "98") (pinfunction "PE1_98") (pintype "passive"))
    )
    (net (code "97") (name "unconnected-(DD5-PE2-Pad1)") (class "Default")
      (node (ref "DD5") (pin "1") (pinfunction "PE2_1") (pintype "passive"))
    )
    (net (code "98") (name "unconnected-(DD5-PE3-Pad2)") (class "Default")
      (node (ref "DD5") (pin "2") (pinfunction "PE3_2") (pintype "passive"))
    )
    (net (code "99") (name "unconnected-(DD5-PE4-Pad3)") (class "Default")
      (node (ref "DD5") (pin "3") (pinfunction "PE4_3") (pintype "passive"))
    )
    (net (code "100") (name "unconnected-(DD5-PE5-Pad4)") (class "Default")
      (node (ref "DD5") (pin "4") (pinfunction "PE5_4") (pintype "passive"))
    )
    (net (code "101") (name "unconnected-(DD5-PE6-Pad5)") (class "Default")
      (node (ref "DD5") (pin "5") (pinfunction "PE6_5") (pintype "passive"))
    )
    (net (code "102") (name "unconnected-(DD5-PE7-Pad37)") (class "Default")
      (node (ref "DD5") (pin "37") (pinfunction "PE7_37") (pintype "passive"))
    )
    (net (code "103") (name "unconnected-(DD5-PE8-Pad38)") (class "Default")
      (node (ref "DD5") (pin "38") (pinfunction "PE8_38") (pintype "passive"))
    )
    (net (code "104") (name "unconnected-(DD5-PE10-Pad40)") (class "Default")
      (node (ref "DD5") (pin "40") (pinfunction "PE10_40") (pintype "passive"))
    )
    (net (code "105") (name "unconnected-(DD5-PE12-Pad42)") (class "Default")
      (node (ref "DD5") (pin "42") (pinfunction "PE12_42") (pintype "passive"))
    )
    (net (code "106") (name "unconnected-(DD5-PE13-Pad43)") (class "Default")
      (node (ref "DD5") (pin "43") (pinfunction "PE13_43") (pintype "passive"))
    )
    (net (code "107") (name "unconnected-(DD5-PE14-Pad44)") (class "Default")
      (node (ref "DD5") (pin "44") (pinfunction "PE14_44") (pintype "passive"))
    )
    (net (code "108") (name "unconnected-(DD5-PE15-Pad45)") (class "Default")
      (node (ref "DD5") (pin "45") (pinfunction "PE15_45") (pintype "passive"))
    )
    (net (code "109") (name "unconnected-(DD5-VBAT-Pad6)") (class "Default")
      (node (ref "DD5") (pin "6") (pinfunction "VBAT_6") (pintype "passive"))
    )
  )
)
